# BK1096_TopLevel.net
KiCad netlist of a schematic drawn in Altium Designer
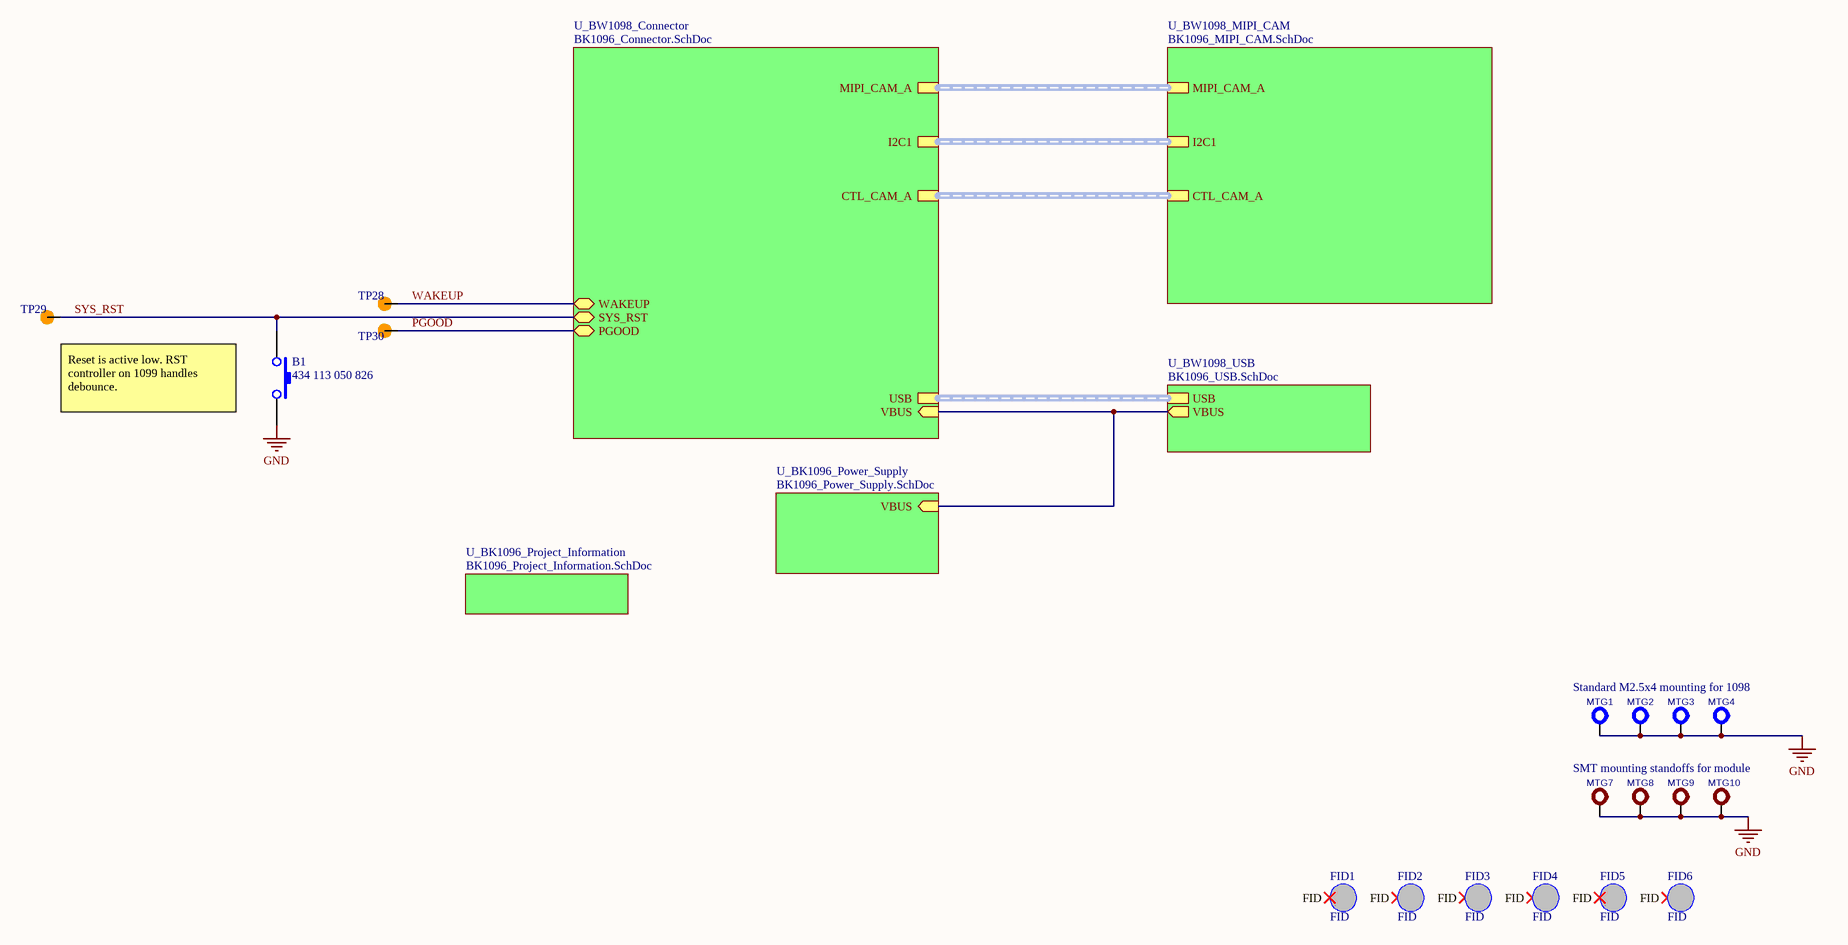
[diagram p0: BK1096_TopLevel.SchDoc]

(export (version "E")
  (design (tool "Eeschema 10.0.6"))
  (components
    (comp (ref "B1")
      (value "434 113 050 826")
      (footprint "Luxonis:DTSM32N")
      (description "Wurth 434 113 050 826")
      (libsource (lib "Luxonis") (part "SW-PB"))
    )
    (comp (ref "FID1")
      (value "FID")
      (footprint "Luxonis:FIDUCIAL_1MM")
      (description "Fiducial mark")
      (libsource (lib "Luxonis") (part "FID"))
    )
    (comp (ref "FID2")
      (value "FID")
      (footprint "Luxonis:FIDUCIAL_1MM")
      (description "Fiducial mark")
      (libsource (lib "Luxonis") (part "FID"))
    )
    (comp (ref "FID3")
      (value "FID")
      (footprint "Luxonis:FIDUCIAL_1MM")
      (description "Fiducial mark")
      (libsource (lib "Luxonis") (part "FID"))
    )
    (comp (ref "FID4")
      (value "FID")
      (footprint "Luxonis:FIDUCIAL_1MM")
      (description "Fiducial mark")
      (libsource (lib "Luxonis") (part "FID"))
    )
    (comp (ref "FID5")
      (value "FID")
      (footprint "Luxonis:FIDUCIAL_1MM")
      (description "Fiducial mark")
      (libsource (lib "Luxonis") (part "FID"))
    )
    (comp (ref "FID6")
      (value "FID")
      (footprint "Luxonis:FIDUCIAL_1MM")
      (description "Fiducial mark")
      (libsource (lib "Luxonis") (part "FID"))
    )
    (comp (ref "MTG1")
      (value "MTG-HOLE")
      (footprint "Luxonis:SCREW_M2.5x4_RPi")
      (description "Mounting Hole")
      (libsource (lib "Luxonis") (part "MTG-HOLE"))
    )
    (comp (ref "MTG2")
      (value "MTG-HOLE")
      (footprint "Luxonis:SCREW_M2.5x4_RPi")
      (description "Mounting Hole")
      (libsource (lib "Luxonis") (part "MTG-HOLE"))
    )
    (comp (ref "MTG3")
      (value "MTG-HOLE")
      (footprint "Luxonis:SCREW_M2.5x4_RPi")
      (description "Mounting Hole")
      (libsource (lib "Luxonis") (part "MTG-HOLE"))
    )
    (comp (ref "MTG4")
      (value "MTG-HOLE")
      (footprint "Luxonis:SCREW_M2.5x4_RPi")
      (description "Mounting Hole")
      (libsource (lib "Luxonis") (part "MTG-HOLE"))
    )
    (comp (ref "MTG7")
      (value "MTG-HOLE")
      (footprint "RS-CONN:STANDOFF_M2X0.4_3MM")
      (description "Mounting Hole")
      (libsource (lib "RS-CONN") (part "MTG-HOLE_B"))
    )
    (comp (ref "MTG8")
      (value "MTG-HOLE")
      (footprint "RS-CONN:STANDOFF_M2X0.4_3MM")
      (description "Mounting Hole")
      (libsource (lib "RS-CONN") (part "MTG-HOLE_B"))
    )
    (comp (ref "MTG9")
      (value "MTG-HOLE")
      (footprint "RS-CONN:STANDOFF_M2X0.4_3MM")
      (description "Mounting Hole")
      (libsource (lib "RS-CONN") (part "MTG-HOLE_B"))
    )
    (comp (ref "MTG10")
      (value "MTG-HOLE")
      (footprint "RS-CONN:STANDOFF_M2X0.4_3MM")
      (description "Mounting Hole")
      (libsource (lib "RS-CONN") (part "MTG-HOLE_B"))
    )
    (comp (ref "TP28")
      (value "TP_SMD")
      (footprint "TP_0.75MM_SMD_NO-SILK")
      (description "circular pad test point, SMD")
      (libsource (lib "Luxonis") (part "TP_SMD"))
    )
    (comp (ref "TP29")
      (value "TP_SMD")
      (footprint "TP_0.75MM_SMD_NO-SILK")
      (description "circular pad test point, SMD")
      (libsource (lib "Luxonis") (part "TP_SMD"))
    )
    (comp (ref "TP30")
      (value "TP_SMD")
      (footprint "TP_0.75MM_SMD_NO-SILK")
      (description "circular pad test point, SMD")
      (libsource (lib "Luxonis") (part "TP_SMD"))
    )
  )
  (nets
    (net (code "4") (name "/PGOOD") (class "Default") (node (ref "TP30") (pin "1") (pintype "passive")))
    (net (code "5") (name "/SYS_RST") (class "Default")
      (node (ref "B1") (pin "1") (pinfunction "1_1") (pintype "passive"))
      (node (ref "TP29") (pin "1") (pintype "passive"))
    )
    (net (code "8") (name "/WAKEUP") (class "Default") (node (ref "TP28") (pin "1") (pintype "passive")))
    (net (code "9") (name "GND") (class "Default")
      (node (ref "B1") (pin "2") (pinfunction "2_2") (pintype "passive"))
      (node (ref "MTG1") (pin "1") (pintype "passive"))
      (node (ref "MTG10") (pin "1") (pintype "passive"))
      (node (ref "MTG2") (pin "1") (pintype "passive"))
      (node (ref "MTG3") (pin "1") (pintype "passive"))
      (node (ref "MTG4") (pin "1") (pintype "passive"))
      (node (ref "MTG7") (pin "1") (pintype "passive"))
      (node (ref "MTG8") (pin "1") (pintype "passive"))
      (node (ref "MTG9") (pin "1") (pintype "passive"))
    )
    (net (code "10") (name "unconnected-(FID1-PadFID)") (class "Default")
      (node (ref "FID1") (pin "FID") (pinfunction "FID_FID") (pintype "input+no_connect"))
    )
    (net (code "11") (name "unconnected-(FID2-PadFID)") (class "Default")
      (node (ref "FID2") (pin "FID") (pinfunction "FID_FID") (pintype "input+no_connect"))
    )
    (net (code "12") (name "unconnected-(FID3-PadFID)") (class "Default")
      (node (ref "FID3") (pin "FID") (pinfunction "FID_FID") (pintype "input+no_connect"))
    )
    (net (code "13") (name "unconnected-(FID4-PadFID)") (class "Default")
      (node (ref "FID4") (pin "FID") (pinfunction "FID_FID") (pintype "input+no_connect"))
    )
    (net (code "14") (name "unconnected-(FID5-PadFID)") (class "Default")
      (node (ref "FID5") (pin "FID") (pinfunction "FID_FID") (pintype "input+no_connect"))
    )
    (net (code "15") (name "unconnected-(FID6-PadFID)") (class "Default")
      (node (ref "FID6") (pin "FID") (pinfunction "FID_FID") (pintype "input+no_connect"))
    )
  )
)
